# EMM.net
KiCad netlist of a schematic drawn in EAGLE
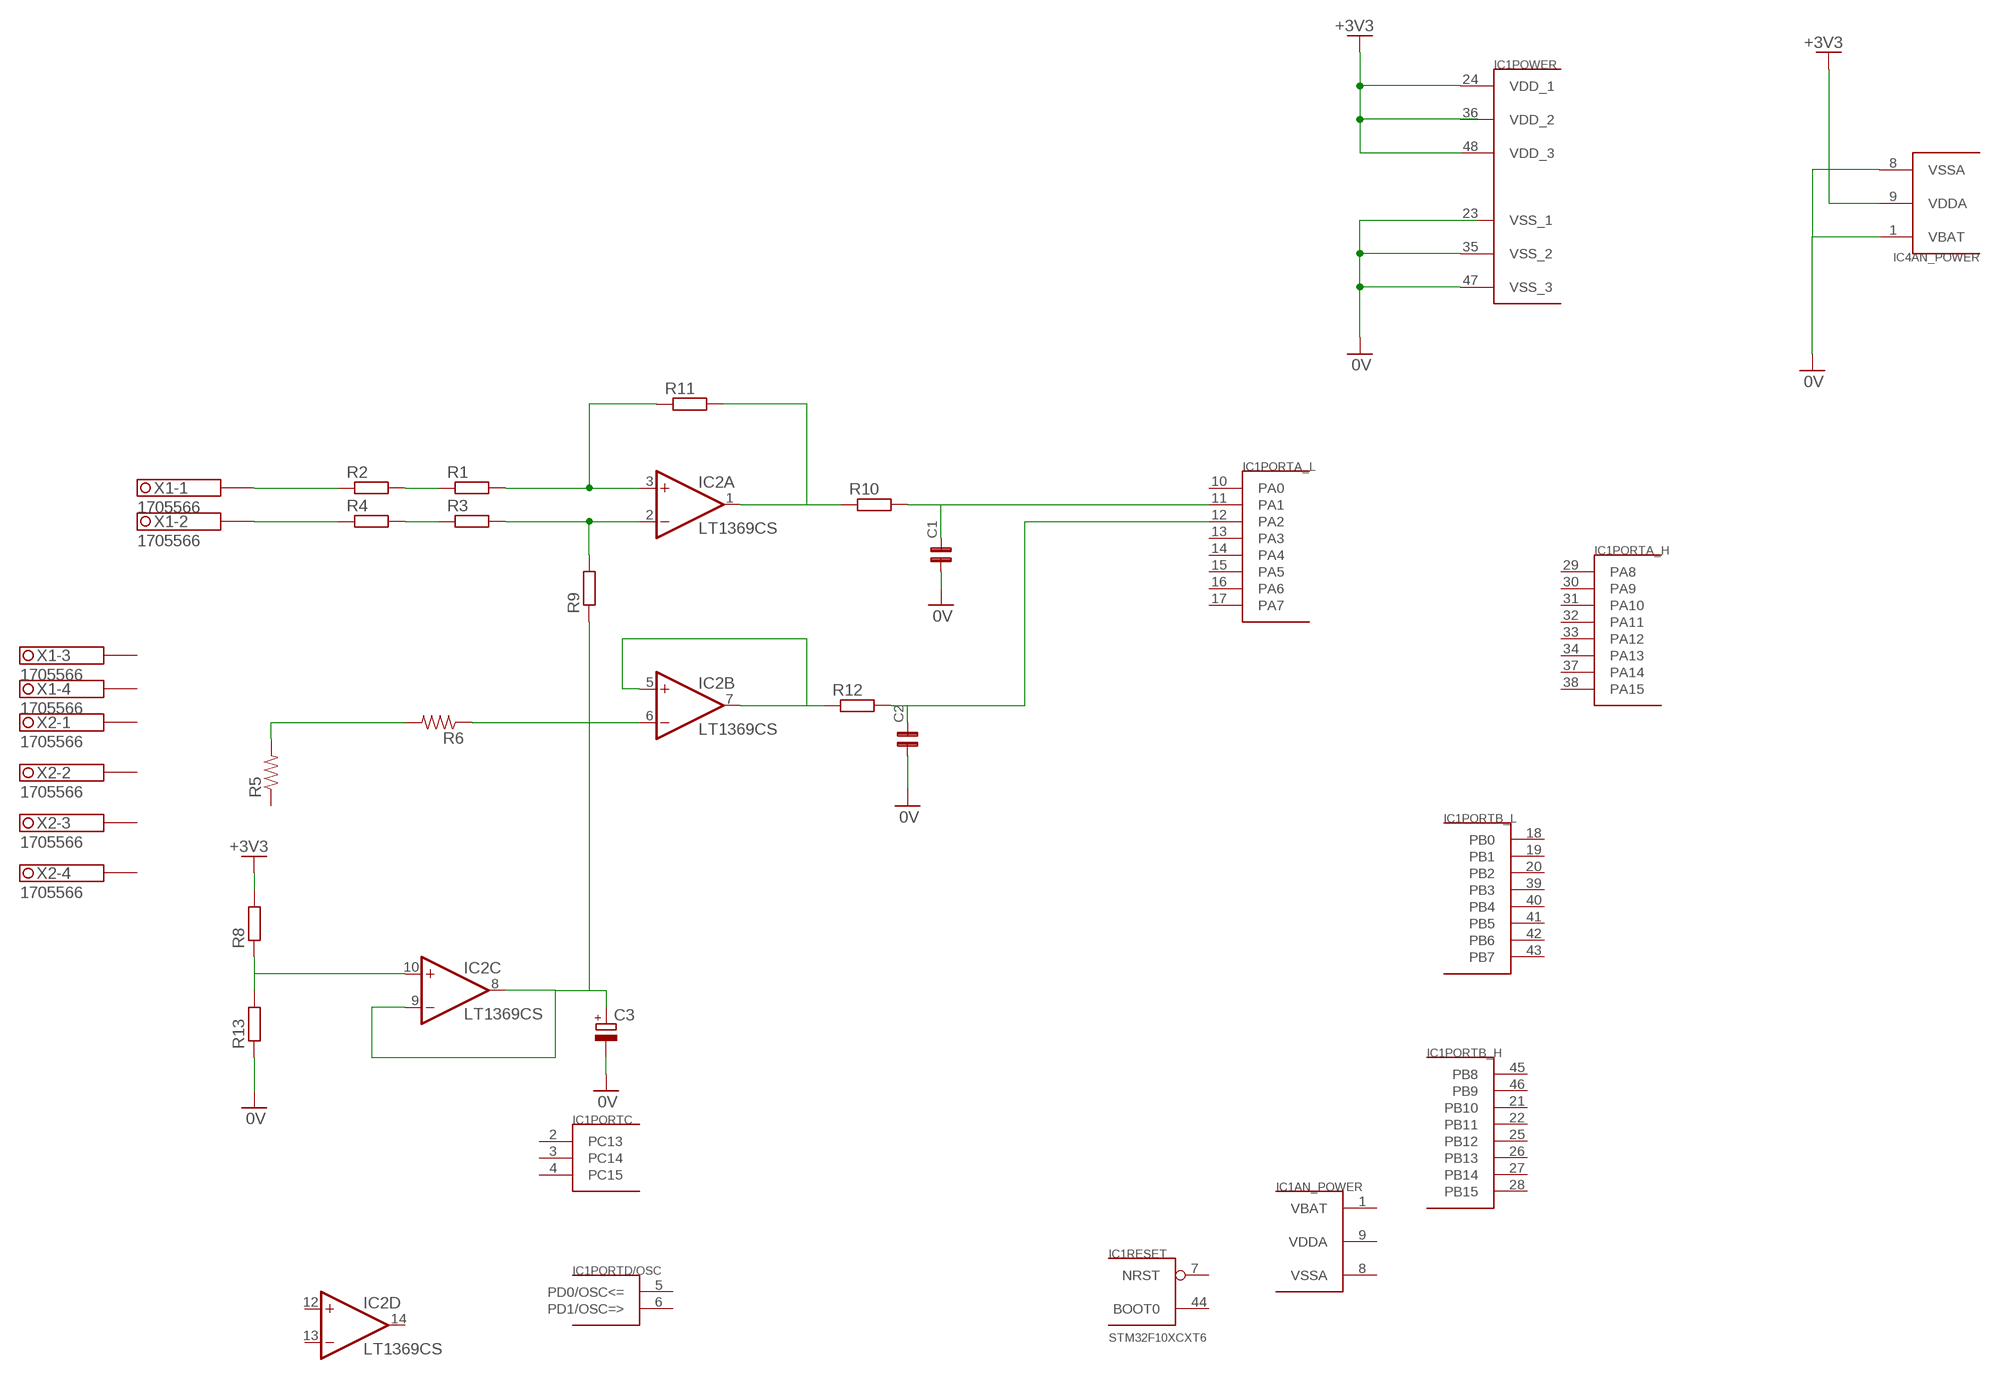
[diagram p0: schematic, sheet 1]

(export (version "E")
  (design (tool "Eeschema 10.0.6"))
  (components
    (comp (ref "C1")
      (value "C0805")
      (footprint "eagle-import:0805")
      (libsource (lib "eagle-import") (part "C0805"))
    )
    (comp (ref "C2")
      (value "C0805")
      (footprint "eagle-import:0805")
      (libsource (lib "eagle-import") (part "C0805"))
    )
    (comp (ref "C3")
      (value "CPOL-EUCT6032")
      (footprint "eagle-import:CT6032")
      (libsource (lib "eagle-import") (part "CPOL-EUCT6032"))
    )
    (comp (ref "IC1")
      (value "STM32F10XCXT6")
      (footprint "eagle-import:TQFP48")
      (libsource (lib "eagle-import") (part "STM32F10XCXT6"))
    )
    (comp (ref "IC2")
      (value "LT1369CS")
      (footprint "eagle-import:SO14")
      (libsource (lib "eagle-import") (part "LT1369SC"))
    )
    (comp (ref "IC4")
      (value "STM32F10XCXT6")
      (footprint "eagle-import:TQFP48")
      (libsource (lib "eagle-import") (part "STM32F10XCXT6"))
    )
    (comp (ref "R1")
      (value "R-EU_0207/10")
      (footprint "eagle-import:0207_10")
      (libsource (lib "eagle-import") (part "R-EU_0207/10"))
    )
    (comp (ref "R2")
      (value "R-EU_0207/10")
      (footprint "eagle-import:0207_10")
      (libsource (lib "eagle-import") (part "R-EU_0207/10"))
    )
    (comp (ref "R3")
      (value "R-EU_0207/10")
      (footprint "eagle-import:0207_10")
      (libsource (lib "eagle-import") (part "R-EU_0207/10"))
    )
    (comp (ref "R4")
      (value "R-EU_0207/10")
      (footprint "eagle-import:0207_10")
      (libsource (lib "eagle-import") (part "R-EU_0207/10"))
    )
    (comp (ref "R5")
      (value "RESISTOR")
      (footprint "eagle-import:0805")
      (libsource (lib "eagle-import") (part "RESISTOR"))
    )
    (comp (ref "R6")
      (value "RESISTOR")
      (footprint "eagle-import:0805")
      (libsource (lib "eagle-import") (part "RESISTOR"))
    )
    (comp (ref "R8")
      (value "R-EU_R0805")
      (footprint "eagle-import:R0805")
      (libsource (lib "eagle-import") (part "R-EU_R0805"))
    )
    (comp (ref "R9")
      (value "R-EU_M0805")
      (footprint "eagle-import:M0805")
      (libsource (lib "eagle-import") (part "R-EU_M0805"))
    )
    (comp (ref "R10")
      (value "R-EU_R0805")
      (footprint "eagle-import:R0805")
      (libsource (lib "eagle-import") (part "R-EU_R0805"))
    )
    (comp (ref "R11")
      (value "R-EU_M0805")
      (footprint "eagle-import:M0805")
      (libsource (lib "eagle-import") (part "R-EU_M0805"))
    )
    (comp (ref "R12")
      (value "R-EU_R0805")
      (footprint "eagle-import:R0805")
      (libsource (lib "eagle-import") (part "R-EU_R0805"))
    )
    (comp (ref "R13")
      (value "R-EU_R0805")
      (footprint "eagle-import:R0805")
      (libsource (lib "eagle-import") (part "R-EU_R0805"))
    )
    (comp (ref "X1")
      (value "1705566")
      (footprint "eagle-import:1705566")
      (libsource (lib "eagle-import") (part "1705566"))
    )
    (comp (ref "X2")
      (value "1705566")
      (footprint "eagle-import:1705566")
      (libsource (lib "eagle-import") (part "1705566"))
    )
  )
  (nets
    (net (code "1") (name "+3V3") (class "Default")
      (node (ref "IC1") (pin "24") (pinfunction "VDD_1_24") (pintype "power_in"))
      (node (ref "IC1") (pin "48") (pinfunction "VDD_3_48") (pintype "power_in"))
      (node (ref "IC4") (pin "9") (pinfunction "VDDA_9") (pintype "power_in"))
      (node (ref "R8") (pin "2") (pinfunction "2_2") (pintype "passive"))
    )
    (net (code "2") (name "/VBAT") (class "Default")
      (node (ref "IC1") (pin "1") (pinfunction "VBAT_1") (pintype "power_in"))
    )
    (net (code "3") (name "/VDDA") (class "Default")
      (node (ref "IC1") (pin "9") (pinfunction "VDDA_9") (pintype "power_in"))
    )
    (net (code "4") (name "/VDD_2") (class "Default")
      (node (ref "IC1") (pin "36") (pinfunction "VDD_2_36") (pintype "power_in"))
    )
    (net (code "5") (name "/VSSA") (class "Default")
      (node (ref "IC1") (pin "8") (pinfunction "VSSA_8") (pintype "power_in"))
    )
    (net (code "6") (name "/VSS_1") (class "Default")
      (node (ref "IC1") (pin "23") (pinfunction "VSS_1_23") (pintype "power_in"))
    )
    (net (code "7") (name "0V") (class "Default")
      (node (ref "C1") (pin "1") (pinfunction "1_1") (pintype "passive"))
      (node (ref "C2") (pin "1") (pinfunction "1_1") (pintype "passive"))
      (node (ref "C3") (pin "-") (pinfunction "-_-") (pintype "passive"))
      (node (ref "IC1") (pin "35") (pinfunction "VSS_2_35") (pintype "power_in"))
      (node (ref "IC1") (pin "47") (pinfunction "VSS_3_47") (pintype "power_in"))
      (node (ref "IC4") (pin "1") (pinfunction "VBAT_1") (pintype "power_in"))
      (node (ref "IC4") (pin "8") (pinfunction "VSSA_8") (pintype "power_in"))
      (node (ref "R13") (pin "1") (pinfunction "1_1") (pintype "passive"))
    )
    (net (code "8") (name "Net-(IC1C-PA1)") (class "Default")
      (node (ref "C1") (pin "2") (pinfunction "2_2") (pintype "passive"))
      (node (ref "IC1") (pin "11") (pinfunction "PA1_11") (pintype "bidirectional"))
      (node (ref "R10") (pin "2") (pinfunction "2_2") (pintype "passive"))
    )
    (net (code "9") (name "Net-(IC1C-PA2)") (class "Default")
      (node (ref "C2") (pin "2") (pinfunction "2_2") (pintype "passive"))
      (node (ref "IC1") (pin "12") (pinfunction "PA2_12") (pintype "bidirectional"))
      (node (ref "R12") (pin "2") (pinfunction "2_2") (pintype "passive"))
    )
    (net (code "10") (name "Net-(IC2A-+IN)") (class "Default")
      (node (ref "IC2") (pin "3") (pinfunction "+IN_3") (pintype "input"))
      (node (ref "R1") (pin "2") (pinfunction "2_2") (pintype "passive"))
      (node (ref "R11") (pin "1") (pinfunction "1_1") (pintype "passive"))
    )
    (net (code "11") (name "Net-(IC2A--IN)") (class "Default")
      (node (ref "IC2") (pin "2") (pinfunction "-IN_2") (pintype "input"))
      (node (ref "R3") (pin "2") (pinfunction "2_2") (pintype "passive"))
      (node (ref "R9") (pin "2") (pinfunction "2_2") (pintype "passive"))
    )
    (net (code "12") (name "Net-(IC2A-OUT)") (class "Default")
      (node (ref "IC2") (pin "1") (pinfunction "OUT_1") (pintype "output"))
      (node (ref "R10") (pin "1") (pinfunction "1_1") (pintype "passive"))
      (node (ref "R11") (pin "2") (pinfunction "2_2") (pintype "passive"))
    )
    (net (code "13") (name "Net-(IC2B-+IN)") (class "Default")
      (node (ref "IC2") (pin "5") (pinfunction "+IN_5") (pintype "input"))
      (node (ref "IC2") (pin "7") (pinfunction "OUT_7") (pintype "output"))
      (node (ref "R12") (pin "1") (pinfunction "1_1") (pintype "passive"))
    )
    (net (code "14") (name "Net-(IC2B--IN)") (class "Default")
      (node (ref "IC2") (pin "6") (pinfunction "-IN_6") (pintype "input"))
      (node (ref "R6") (pin "1") (pinfunction "1_1") (pintype "passive"))
    )
    (net (code "15") (name "Net-(IC2C-+IN)") (class "Default")
      (node (ref "IC2") (pin "10") (pinfunction "+IN_10") (pintype "input"))
      (node (ref "R13") (pin "2") (pinfunction "2_2") (pintype "passive"))
      (node (ref "R8") (pin "1") (pinfunction "1_1") (pintype "passive"))
    )
    (net (code "16") (name "Net-(IC2C--IN)") (class "Default")
      (node (ref "C3") (pin "+") (pinfunction "+_+") (pintype "passive"))
      (node (ref "IC2") (pin "8") (pinfunction "OUT_8") (pintype "output"))
      (node (ref "IC2") (pin "9") (pinfunction "-IN_9") (pintype "input"))
      (node (ref "R9") (pin "1") (pinfunction "1_1") (pintype "passive"))
    )
    (net (code "17") (name "Net-(R1-Pad1)") (class "Default")
      (node (ref "R1") (pin "1") (pinfunction "1_1") (pintype "passive"))
      (node (ref "R2") (pin "2") (pinfunction "2_2") (pintype "passive"))
    )
    (net (code "18") (name "Net-(R3-Pad1)") (class "Default")
      (node (ref "R3") (pin "1") (pinfunction "1_1") (pintype "passive"))
      (node (ref "R4") (pin "2") (pinfunction "2_2") (pintype "passive"))
    )
    (net (code "19") (name "Net-(R5-Pad2)") (class "Default")
      (node (ref "R5") (pin "2") (pinfunction "2_2") (pintype "passive"))
      (node (ref "R6") (pin "2") (pinfunction "2_2") (pintype "passive"))
    )
    (net (code "20") (name "Net-(X1A-1B)") (class "Default")
      (node (ref "R2") (pin "1") (pinfunction "1_1") (pintype "passive"))
      (node (ref "X1") (pin "1.2") (pinfunction "1B_1.2") (pintype "passive"))
    )
    (net (code "21") (name "Net-(X1B-1B)") (class "Default")
      (node (ref "R4") (pin "1") (pinfunction "1_1") (pintype "passive"))
      (node (ref "X1") (pin "2.2") (pinfunction "1B_2.2") (pintype "passive"))
    )
    (net (code "22") (name "unconnected-(IC1B-PA8-Pad29)") (class "Default")
      (node (ref "IC1") (pin "29") (pinfunction "PA8_29") (pintype "bidirectional"))
    )
    (net (code "23") (name "unconnected-(IC1B-PA9-Pad30)") (class "Default")
      (node (ref "IC1") (pin "30") (pinfunction "PA9_30") (pintype "bidirectional"))
    )
    (net (code "24") (name "unconnected-(IC1B-PA10-Pad31)") (class "Default")
      (node (ref "IC1") (pin "31") (pinfunction "PA10_31") (pintype "bidirectional"))
    )
    (net (code "25") (name "unconnected-(IC1B-PA11-Pad32)") (class "Default")
      (node (ref "IC1") (pin "32") (pinfunction "PA11_32") (pintype "bidirectional"))
    )
    (net (code "26") (name "unconnected-(IC1B-PA12-Pad33)") (class "Default")
      (node (ref "IC1") (pin "33") (pinfunction "PA12_33") (pintype "bidirectional"))
    )
    (net (code "27") (name "unconnected-(IC1B-PA13-Pad34)") (class "Default")
      (node (ref "IC1") (pin "34") (pinfunction "PA13_34") (pintype "bidirectional"))
    )
    (net (code "28") (name "unconnected-(IC1B-PA14-Pad37)") (class "Default")
      (node (ref "IC1") (pin "37") (pinfunction "PA14_37") (pintype "bidirectional"))
    )
    (net (code "29") (name "unconnected-(IC1B-PA15-Pad38)") (class "Default")
      (node (ref "IC1") (pin "38") (pinfunction "PA15_38") (pintype "bidirectional"))
    )
    (net (code "30") (name "unconnected-(IC1C-PA0-Pad10)") (class "Default")
      (node (ref "IC1") (pin "10") (pinfunction "PA0_10") (pintype "bidirectional"))
    )
    (net (code "31") (name "unconnected-(IC1C-PA3-Pad13)") (class "Default")
      (node (ref "IC1") (pin "13") (pinfunction "PA3_13") (pintype "bidirectional"))
    )
    (net (code "32") (name "unconnected-(IC1C-PA4-Pad14)") (class "Default")
      (node (ref "IC1") (pin "14") (pinfunction "PA4_14") (pintype "bidirectional"))
    )
    (net (code "33") (name "unconnected-(IC1C-PA5-Pad15)") (class "Default")
      (node (ref "IC1") (pin "15") (pinfunction "PA5_15") (pintype "bidirectional"))
    )
    (net (code "34") (name "unconnected-(IC1C-PA6-Pad16)") (class "Default")
      (node (ref "IC1") (pin "16") (pinfunction "PA6_16") (pintype "bidirectional"))
    )
    (net (code "35") (name "unconnected-(IC1C-PA7-Pad17)") (class "Default")
      (node (ref "IC1") (pin "17") (pinfunction "PA7_17") (pintype "bidirectional"))
    )
    (net (code "36") (name "unconnected-(IC1D-PB8-Pad45)") (class "Default")
      (node (ref "IC1") (pin "45") (pinfunction "PB8_45") (pintype "bidirectional"))
    )
    (net (code "37") (name "unconnected-(IC1D-PB9-Pad46)") (class "Default")
      (node (ref "IC1") (pin "46") (pinfunction "PB9_46") (pintype "bidirectional"))
    )
    (net (code "38") (name "unconnected-(IC1D-PB10-Pad21)") (class "Default")
      (node (ref "IC1") (pin "21") (pinfunction "PB10_21") (pintype "bidirectional"))
    )
    (net (code "39") (name "unconnected-(IC1D-PB11-Pad22)") (class "Default")
      (node (ref "IC1") (pin "22") (pinfunction "PB11_22") (pintype "bidirectional"))
    )
    (net (code "40") (name "unconnected-(IC1D-PB12-Pad25)") (class "Default")
      (node (ref "IC1") (pin "25") (pinfunction "PB12_25") (pintype "bidirectional"))
    )
    (net (code "41") (name "unconnected-(IC1D-PB13-Pad26)") (class "Default")
      (node (ref "IC1") (pin "26") (pinfunction "PB13_26") (pintype "bidirectional"))
    )
    (net (code "42") (name "unconnected-(IC1D-PB14-Pad27)") (class "Default")
      (node (ref "IC1") (pin "27") (pinfunction "PB14_27") (pintype "bidirectional"))
    )
    (net (code "43") (name "unconnected-(IC1D-PB15-Pad28)") (class "Default")
      (node (ref "IC1") (pin "28") (pinfunction "PB15_28") (pintype "bidirectional"))
    )
    (net (code "44") (name "unconnected-(IC1E-PB0-Pad18)") (class "Default")
      (node (ref "IC1") (pin "18") (pinfunction "PB0_18") (pintype "bidirectional"))
    )
    (net (code "45") (name "unconnected-(IC1E-PB1-Pad19)") (class "Default")
      (node (ref "IC1") (pin "19") (pinfunction "PB1_19") (pintype "bidirectional"))
    )
    (net (code "46") (name "unconnected-(IC1E-PB2-Pad20)") (class "Default")
      (node (ref "IC1") (pin "20") (pinfunction "PB2_20") (pintype "bidirectional"))
    )
    (net (code "47") (name "unconnected-(IC1E-PB3-Pad39)") (class "Default")
      (node (ref "IC1") (pin "39") (pinfunction "PB3_39") (pintype "bidirectional"))
    )
    (net (code "48") (name "unconnected-(IC1E-PB4-Pad40)") (class "Default")
      (node (ref "IC1") (pin "40") (pinfunction "PB4_40") (pintype "bidirectional"))
    )
    (net (code "49") (name "unconnected-(IC1E-PB5-Pad41)") (class "Default")
      (node (ref "IC1") (pin "41") (pinfunction "PB5_41") (pintype "bidirectional"))
    )
    (net (code "50") (name "unconnected-(IC1E-PB6-Pad42)") (class "Default")
      (node (ref "IC1") (pin "42") (pinfunction "PB6_42") (pintype "bidirectional"))
    )
    (net (code "51") (name "unconnected-(IC1E-PB7-Pad43)") (class "Default")
      (node (ref "IC1") (pin "43") (pinfunction "PB7_43") (pintype "bidirectional"))
    )
    (net (code "52") (name "unconnected-(IC1F-PC13-Pad2)") (class "Default")
      (node (ref "IC1") (pin "2") (pinfunction "PC13_2") (pintype "bidirectional"))
    )
    (net (code "53") (name "unconnected-(IC1F-PC14-Pad3)") (class "Default")
      (node (ref "IC1") (pin "3") (pinfunction "PC14_3") (pintype "bidirectional"))
    )
    (net (code "54") (name "unconnected-(IC1F-PC15-Pad4)") (class "Default")
      (node (ref "IC1") (pin "4") (pinfunction "PC15_4") (pintype "bidirectional"))
    )
    (net (code "55") (name "unconnected-(IC1G-PD0{slash}OSC<=-Pad5)") (class "Default")
      (node (ref "IC1") (pin "5") (pinfunction "PD0/OSC<=_5") (pintype "bidirectional"))
    )
    (net (code "56") (name "unconnected-(IC1G-PD1{slash}OSC=>-Pad6)") (class "Default")
      (node (ref "IC1") (pin "6") (pinfunction "PD1/OSC=>_6") (pintype "bidirectional"))
    )
    (net (code "57") (name "unconnected-(IC1I-BOOT0-Pad44)") (class "Default")
      (node (ref "IC1") (pin "44") (pinfunction "BOOT0_44") (pintype "input"))
    )
    (net (code "58") (name "unconnected-(IC1I-NRST-Pad7)") (class "Default")
      (node (ref "IC1") (pin "7") (pinfunction "NRST_7") (pintype "input"))
    )
    (net (code "59") (name "unconnected-(IC2D-+IN-Pad12)") (class "Default")
      (node (ref "IC2") (pin "12") (pinfunction "+IN_12") (pintype "input"))
    )
    (net (code "60") (name "unconnected-(IC2D--IN-Pad13)") (class "Default")
      (node (ref "IC2") (pin "13") (pinfunction "-IN_13") (pintype "input"))
    )
    (net (code "61") (name "unconnected-(IC2D-OUT-Pad14)") (class "Default")
      (node (ref "IC2") (pin "14") (pinfunction "OUT_14") (pintype "output"))
    )
    (net (code "62") (name "unconnected-(R5-Pad1)") (class "Default")
      (node (ref "R5") (pin "1") (pinfunction "1_1") (pintype "passive"))
    )
    (net (code "63") (name "unconnected-(X1A-1A-Pad1.1)") (class "Default")
      (node (ref "X1") (pin "1.1") (pinfunction "1A_1.1") (pintype "passive"))
    )
    (net (code "64") (name "unconnected-(X1B-1A-Pad2.1)") (class "Default")
      (node (ref "X1") (pin "2.1") (pinfunction "1A_2.1") (pintype "passive"))
    )
    (net (code "65") (name "unconnected-(X1C-1A-Pad3.1)") (class "Default")
      (node (ref "X1") (pin "3.1") (pinfunction "1A_3.1") (pintype "passive"))
    )
    (net (code "66") (name "unconnected-(X1C-1B-Pad3.2)") (class "Default")
      (node (ref "X1") (pin "3.2") (pinfunction "1B_3.2") (pintype "passive"))
    )
    (net (code "67") (name "unconnected-(X1D-1A-Pad4.1)") (class "Default")
      (node (ref "X1") (pin "4.1") (pinfunction "1A_4.1") (pintype "passive"))
    )
    (net (code "68") (name "unconnected-(X1D-1B-Pad4.2)") (class "Default")
      (node (ref "X1") (pin "4.2") (pinfunction "1B_4.2") (pintype "passive"))
    )
    (net (code "69") (name "unconnected-(X2A-1A-Pad1.1)") (class "Default")
      (node (ref "X2") (pin "1.1") (pinfunction "1A_1.1") (pintype "passive"))
    )
    (net (code "70") (name "unconnected-(X2A-1B-Pad1.2)") (class "Default")
      (node (ref "X2") (pin "1.2") (pinfunction "1B_1.2") (pintype "passive"))
    )
    (net (code "71") (name "unconnected-(X2B-1A-Pad2.1)") (class "Default")
      (node (ref "X2") (pin "2.1") (pinfunction "1A_2.1") (pintype "passive"))
    )
    (net (code "72") (name "unconnected-(X2B-1B-Pad2.2)") (class "Default")
      (node (ref "X2") (pin "2.2") (pinfunction "1B_2.2") (pintype "passive"))
    )
    (net (code "73") (name "unconnected-(X2C-1A-Pad3.1)") (class "Default")
      (node (ref "X2") (pin "3.1") (pinfunction "1A_3.1") (pintype "passive"))
    )
    (net (code "74") (name "unconnected-(X2C-1B-Pad3.2)") (class "Default")
      (node (ref "X2") (pin "3.2") (pinfunction "1B_3.2") (pintype "passive"))
    )
    (net (code "75") (name "unconnected-(X2D-1A-Pad4.1)") (class "Default")
      (node (ref "X2") (pin "4.1") (pinfunction "1A_4.1") (pintype "passive"))
    )
    (net (code "76") (name "unconnected-(X2D-1B-Pad4.2)") (class "Default")
      (node (ref "X2") (pin "4.2") (pinfunction "1B_4.2") (pintype "passive"))
    )
  )
)
